# nixie_-_final1.net
KiCad netlist of a schematic drawn in EAGLE
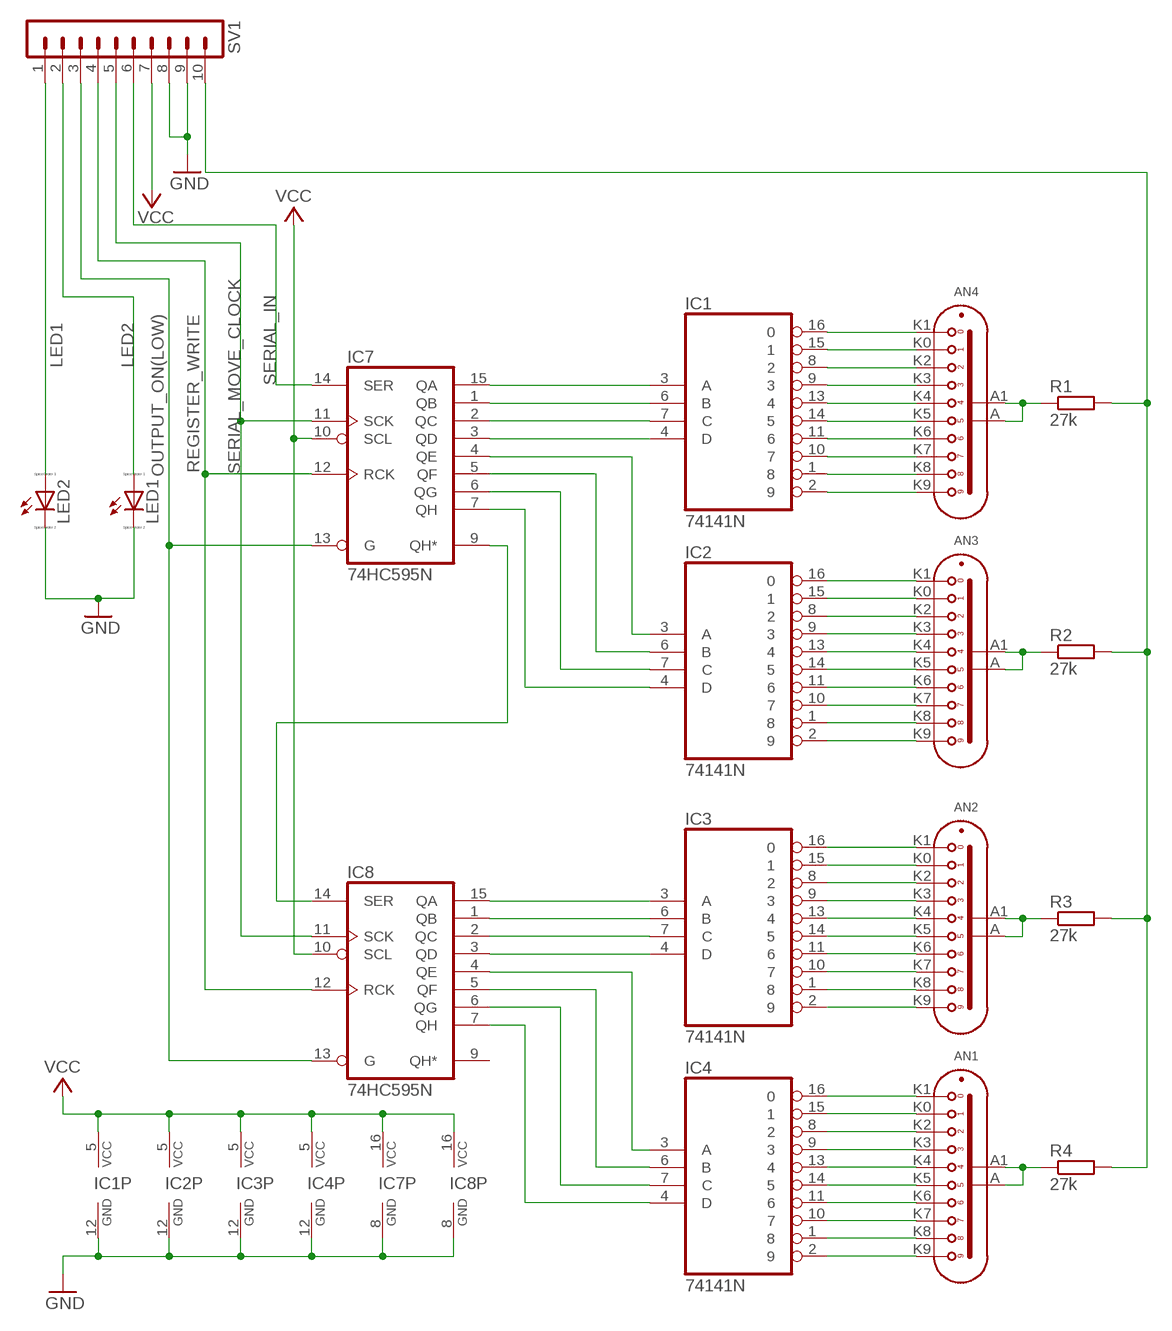
[diagram p0: schematic, sheet 1]

(export (version "E")
  (design (tool "Eeschema 10.0.6"))
  (components
    (comp (ref "AN1")
      (value "ZM1042-SOCKET_ELRADO")
      (footprint "eagle-import:ZM1040.SOCKET")
      (libsource (lib "eagle-import") (part "ZM1042-SOCKET_ELRADO"))
    )
    (comp (ref "AN2")
      (value "ZM1042-SOCKET_ELRADO")
      (footprint "eagle-import:ZM1040.SOCKET")
      (libsource (lib "eagle-import") (part "ZM1042-SOCKET_ELRADO"))
    )
    (comp (ref "AN3")
      (value "ZM1042-SOCKET_ELRADO")
      (footprint "eagle-import:ZM1040.SOCKET")
      (libsource (lib "eagle-import") (part "ZM1042-SOCKET_ELRADO"))
    )
    (comp (ref "AN4")
      (value "ZM1042-SOCKET_ELRADO")
      (footprint "eagle-import:ZM1040.SOCKET")
      (libsource (lib "eagle-import") (part "ZM1042-SOCKET_ELRADO"))
    )
    (comp (ref "IC1")
      (value "74141N")
      (footprint "eagle-import:DIL16")
      (libsource (lib "eagle-import") (part "74141N"))
    )
    (comp (ref "IC2")
      (value "74141N")
      (footprint "eagle-import:DIL16")
      (libsource (lib "eagle-import") (part "74141N"))
    )
    (comp (ref "IC3")
      (value "74141N")
      (footprint "eagle-import:DIL16")
      (libsource (lib "eagle-import") (part "74141N"))
    )
    (comp (ref "IC4")
      (value "74141N")
      (footprint "eagle-import:DIL16")
      (libsource (lib "eagle-import") (part "74141N"))
    )
    (comp (ref "IC7")
      (value "74HC595N")
      (footprint "eagle-import:DIL16")
      (libsource (lib "eagle-import") (part "74595NHC"))
    )
    (comp (ref "IC8")
      (value "74HC595N")
      (footprint "eagle-import:DIL16")
      (libsource (lib "eagle-import") (part "74595NHC"))
    )
    (comp (ref "LED1")
      (value "LED_ELD260")
      (footprint "eagle-import:LED_LD260")
      (libsource (lib "eagle-import") (part "LED_ELD260"))
    )
    (comp (ref "LED2")
      (value "LED_ELD260")
      (footprint "eagle-import:LED_LD260")
      (libsource (lib "eagle-import") (part "LED_ELD260"))
    )
    (comp (ref "R1")
      (value "27k")
      (footprint "eagle-import:0309_12")
      (libsource (lib "eagle-import") (part "R-EU_0309/12"))
    )
    (comp (ref "R2")
      (value "27k")
      (footprint "eagle-import:0309_12")
      (libsource (lib "eagle-import") (part "R-EU_0309/12"))
    )
    (comp (ref "R3")
      (value "27k")
      (footprint "eagle-import:0309_12")
      (libsource (lib "eagle-import") (part "R-EU_0309/12"))
    )
    (comp (ref "R4")
      (value "27k")
      (footprint "eagle-import:0309_12")
      (libsource (lib "eagle-import") (part "R-EU_0309/12"))
    )
    (comp (ref "SV1")
      (value "MA10-1")
      (footprint "eagle-import:MA10-1")
      (libsource (lib "eagle-import") (part "MA10-1"))
    )
  )
  (nets
    (net (code "1") (name "/LED1") (class "Default")
      (node (ref "LED2") (pin "A") (pinfunction "A_A") (pintype "passive"))
      (node (ref "SV1") (pin "1") (pinfunction "1_1") (pintype "passive"))
    )
    (net (code "2") (name "/LED2") (class "Default")
      (node (ref "LED1") (pin "A") (pinfunction "A_A") (pintype "passive"))
      (node (ref "SV1") (pin "2") (pinfunction "2_2") (pintype "passive"))
    )
    (net (code "3") (name "/OUTPUT_ON(LOW)") (class "Default")
      (node (ref "IC7") (pin "13") (pinfunction "G_13") (pintype "input"))
      (node (ref "IC8") (pin "13") (pinfunction "G_13") (pintype "input"))
      (node (ref "SV1") (pin "3") (pinfunction "3_3") (pintype "passive"))
    )
    (net (code "4") (name "/REGISTER_WRITE") (class "Default")
      (node (ref "IC7") (pin "12") (pinfunction "RCK_12") (pintype "input"))
      (node (ref "IC8") (pin "12") (pinfunction "RCK_12") (pintype "input"))
      (node (ref "SV1") (pin "4") (pinfunction "4_4") (pintype "passive"))
    )
    (net (code "5") (name "/SERIAL_IN") (class "Default")
      (node (ref "IC7") (pin "14") (pinfunction "SER_14") (pintype "input"))
      (node (ref "SV1") (pin "6") (pinfunction "6_6") (pintype "passive"))
    )
    (net (code "6") (name "/SERIAL_MOVE_CLOCK") (class "Default")
      (node (ref "IC7") (pin "11") (pinfunction "SCK_11") (pintype "input"))
      (node (ref "IC8") (pin "11") (pinfunction "SCK_11") (pintype "input"))
      (node (ref "SV1") (pin "5") (pinfunction "5_5") (pintype "passive"))
    )
    (net (code "7") (name "GND") (class "Default")
      (node (ref "IC1") (pin "12") (pinfunction "GND_12") (pintype "power_in"))
      (node (ref "IC2") (pin "12") (pinfunction "GND_12") (pintype "power_in"))
      (node (ref "IC3") (pin "12") (pinfunction "GND_12") (pintype "power_in"))
      (node (ref "IC4") (pin "12") (pinfunction "GND_12") (pintype "power_in"))
      (node (ref "IC7") (pin "8") (pinfunction "GND_8") (pintype "power_in"))
      (node (ref "IC8") (pin "8") (pinfunction "GND_8") (pintype "power_in"))
      (node (ref "LED1") (pin "K") (pinfunction "C_K") (pintype "passive"))
      (node (ref "LED2") (pin "K") (pinfunction "C_K") (pintype "passive"))
      (node (ref "SV1") (pin "8") (pinfunction "8_8") (pintype "passive"))
      (node (ref "SV1") (pin "9") (pinfunction "9_9") (pintype "passive"))
    )
    (net (code "8") (name "Net-(AN1-0)") (class "Default")
      (node (ref "AN1") (pin "K1") (pinfunction "0_K1") (pintype "passive"))
      (node (ref "IC4") (pin "16") (pinfunction "0_16") (pintype "open_collector"))
    )
    (net (code "9") (name "Net-(AN1-1)") (class "Default")
      (node (ref "AN1") (pin "K0") (pinfunction "1_K0") (pintype "passive"))
      (node (ref "IC4") (pin "15") (pinfunction "1_15") (pintype "open_collector"))
    )
    (net (code "10") (name "Net-(AN1-2)") (class "Default")
      (node (ref "AN1") (pin "K2") (pinfunction "2_K2") (pintype "passive"))
      (node (ref "IC4") (pin "8") (pinfunction "2_8") (pintype "open_collector"))
    )
    (net (code "11") (name "Net-(AN1-3)") (class "Default")
      (node (ref "AN1") (pin "K3") (pinfunction "3_K3") (pintype "passive"))
      (node (ref "IC4") (pin "9") (pinfunction "3_9") (pintype "open_collector"))
    )
    (net (code "12") (name "Net-(AN1-4)") (class "Default")
      (node (ref "AN1") (pin "K4") (pinfunction "4_K4") (pintype "passive"))
      (node (ref "IC4") (pin "13") (pinfunction "4_13") (pintype "open_collector"))
    )
    (net (code "13") (name "Net-(AN1-5)") (class "Default")
      (node (ref "AN1") (pin "K5") (pinfunction "5_K5") (pintype "passive"))
      (node (ref "IC4") (pin "14") (pinfunction "5_14") (pintype "open_collector"))
    )
    (net (code "14") (name "Net-(AN1-6)") (class "Default")
      (node (ref "AN1") (pin "K6") (pinfunction "6_K6") (pintype "passive"))
      (node (ref "IC4") (pin "11") (pinfunction "6_11") (pintype "open_collector"))
    )
    (net (code "15") (name "Net-(AN1-7)") (class "Default")
      (node (ref "AN1") (pin "K7") (pinfunction "7_K7") (pintype "passive"))
      (node (ref "IC4") (pin "10") (pinfunction "7_10") (pintype "open_collector"))
    )
    (net (code "16") (name "Net-(AN1-8)") (class "Default")
      (node (ref "AN1") (pin "K8") (pinfunction "8_K8") (pintype "passive"))
      (node (ref "IC4") (pin "1") (pinfunction "8_1") (pintype "open_collector"))
    )
    (net (code "17") (name "Net-(AN1-9)") (class "Default")
      (node (ref "AN1") (pin "K9") (pinfunction "9_K9") (pintype "passive"))
      (node (ref "IC4") (pin "2") (pinfunction "9_2") (pintype "open_collector"))
    )
    (net (code "18") (name "Net-(AN1-A1)") (class "Default")
      (node (ref "AN1") (pin "A") (pinfunction "A1_A") (pintype "passive"))
      (node (ref "AN1") (pin "A1") (pinfunction "A2_A1") (pintype "passive"))
      (node (ref "R4") (pin "1") (pinfunction "1_1") (pintype "passive"))
    )
    (net (code "19") (name "Net-(AN2-0)") (class "Default")
      (node (ref "AN2") (pin "K1") (pinfunction "0_K1") (pintype "passive"))
      (node (ref "IC3") (pin "16") (pinfunction "0_16") (pintype "open_collector"))
    )
    (net (code "20") (name "Net-(AN2-1)") (class "Default")
      (node (ref "AN2") (pin "K0") (pinfunction "1_K0") (pintype "passive"))
      (node (ref "IC3") (pin "15") (pinfunction "1_15") (pintype "open_collector"))
    )
    (net (code "21") (name "Net-(AN2-2)") (class "Default")
      (node (ref "AN2") (pin "K2") (pinfunction "2_K2") (pintype "passive"))
      (node (ref "IC3") (pin "8") (pinfunction "2_8") (pintype "open_collector"))
    )
    (net (code "22") (name "Net-(AN2-3)") (class "Default")
      (node (ref "AN2") (pin "K3") (pinfunction "3_K3") (pintype "passive"))
      (node (ref "IC3") (pin "9") (pinfunction "3_9") (pintype "open_collector"))
    )
    (net (code "23") (name "Net-(AN2-4)") (class "Default")
      (node (ref "AN2") (pin "K4") (pinfunction "4_K4") (pintype "passive"))
      (node (ref "IC3") (pin "13") (pinfunction "4_13") (pintype "open_collector"))
    )
    (net (code "24") (name "Net-(AN2-5)") (class "Default")
      (node (ref "AN2") (pin "K5") (pinfunction "5_K5") (pintype "passive"))
      (node (ref "IC3") (pin "14") (pinfunction "5_14") (pintype "open_collector"))
    )
    (net (code "25") (name "Net-(AN2-6)") (class "Default")
      (node (ref "AN2") (pin "K6") (pinfunction "6_K6") (pintype "passive"))
      (node (ref "IC3") (pin "11") (pinfunction "6_11") (pintype "open_collector"))
    )
    (net (code "26") (name "Net-(AN2-7)") (class "Default")
      (node (ref "AN2") (pin "K7") (pinfunction "7_K7") (pintype "passive"))
      (node (ref "IC3") (pin "10") (pinfunction "7_10") (pintype "open_collector"))
    )
    (net (code "27") (name "Net-(AN2-8)") (class "Default")
      (node (ref "AN2") (pin "K8") (pinfunction "8_K8") (pintype "passive"))
      (node (ref "IC3") (pin "1") (pinfunction "8_1") (pintype "open_collector"))
    )
    (net (code "28") (name "Net-(AN2-9)") (class "Default")
      (node (ref "AN2") (pin "K9") (pinfunction "9_K9") (pintype "passive"))
      (node (ref "IC3") (pin "2") (pinfunction "9_2") (pintype "open_collector"))
    )
    (net (code "29") (name "Net-(AN2-A1)") (class "Default")
      (node (ref "AN2") (pin "A") (pinfunction "A1_A") (pintype "passive"))
      (node (ref "AN2") (pin "A1") (pinfunction "A2_A1") (pintype "passive"))
      (node (ref "R3") (pin "1") (pinfunction "1_1") (pintype "passive"))
    )
    (net (code "30") (name "Net-(AN3-0)") (class "Default")
      (node (ref "AN3") (pin "K1") (pinfunction "0_K1") (pintype "passive"))
      (node (ref "IC2") (pin "16") (pinfunction "0_16") (pintype "open_collector"))
    )
    (net (code "31") (name "Net-(AN3-1)") (class "Default")
      (node (ref "AN3") (pin "K0") (pinfunction "1_K0") (pintype "passive"))
      (node (ref "IC2") (pin "15") (pinfunction "1_15") (pintype "open_collector"))
    )
    (net (code "32") (name "Net-(AN3-2)") (class "Default")
      (node (ref "AN3") (pin "K2") (pinfunction "2_K2") (pintype "passive"))
      (node (ref "IC2") (pin "8") (pinfunction "2_8") (pintype "open_collector"))
    )
    (net (code "33") (name "Net-(AN3-3)") (class "Default")
      (node (ref "AN3") (pin "K3") (pinfunction "3_K3") (pintype "passive"))
      (node (ref "IC2") (pin "9") (pinfunction "3_9") (pintype "open_collector"))
    )
    (net (code "34") (name "Net-(AN3-4)") (class "Default")
      (node (ref "AN3") (pin "K4") (pinfunction "4_K4") (pintype "passive"))
      (node (ref "IC2") (pin "13") (pinfunction "4_13") (pintype "open_collector"))
    )
    (net (code "35") (name "Net-(AN3-5)") (class "Default")
      (node (ref "AN3") (pin "K5") (pinfunction "5_K5") (pintype "passive"))
      (node (ref "IC2") (pin "14") (pinfunction "5_14") (pintype "open_collector"))
    )
    (net (code "36") (name "Net-(AN3-6)") (class "Default")
      (node (ref "AN3") (pin "K6") (pinfunction "6_K6") (pintype "passive"))
      (node (ref "IC2") (pin "11") (pinfunction "6_11") (pintype "open_collector"))
    )
    (net (code "37") (name "Net-(AN3-7)") (class "Default")
      (node (ref "AN3") (pin "K7") (pinfunction "7_K7") (pintype "passive"))
      (node (ref "IC2") (pin "10") (pinfunction "7_10") (pintype "open_collector"))
    )
    (net (code "38") (name "Net-(AN3-8)") (class "Default")
      (node (ref "AN3") (pin "K8") (pinfunction "8_K8") (pintype "passive"))
      (node (ref "IC2") (pin "1") (pinfunction "8_1") (pintype "open_collector"))
    )
    (net (code "39") (name "Net-(AN3-9)") (class "Default")
      (node (ref "AN3") (pin "K9") (pinfunction "9_K9") (pintype "passive"))
      (node (ref "IC2") (pin "2") (pinfunction "9_2") (pintype "open_collector"))
    )
    (net (code "40") (name "Net-(AN3-A1)") (class "Default")
      (node (ref "AN3") (pin "A") (pinfunction "A1_A") (pintype "passive"))
      (node (ref "AN3") (pin "A1") (pinfunction "A2_A1") (pintype "passive"))
      (node (ref "R2") (pin "1") (pinfunction "1_1") (pintype "passive"))
    )
    (net (code "41") (name "Net-(AN4-0)") (class "Default")
      (node (ref "AN4") (pin "K1") (pinfunction "0_K1") (pintype "passive"))
      (node (ref "IC1") (pin "16") (pinfunction "0_16") (pintype "open_collector"))
    )
    (net (code "42") (name "Net-(AN4-1)") (class "Default")
      (node (ref "AN4") (pin "K0") (pinfunction "1_K0") (pintype "passive"))
      (node (ref "IC1") (pin "15") (pinfunction "1_15") (pintype "open_collector"))
    )
    (net (code "43") (name "Net-(AN4-2)") (class "Default")
      (node (ref "AN4") (pin "K2") (pinfunction "2_K2") (pintype "passive"))
      (node (ref "IC1") (pin "8") (pinfunction "2_8") (pintype "open_collector"))
    )
    (net (code "44") (name "Net-(AN4-3)") (class "Default")
      (node (ref "AN4") (pin "K3") (pinfunction "3_K3") (pintype "passive"))
      (node (ref "IC1") (pin "9") (pinfunction "3_9") (pintype "open_collector"))
    )
    (net (code "45") (name "Net-(AN4-4)") (class "Default")
      (node (ref "AN4") (pin "K4") (pinfunction "4_K4") (pintype "passive"))
      (node (ref "IC1") (pin "13") (pinfunction "4_13") (pintype "open_collector"))
    )
    (net (code "46") (name "Net-(AN4-5)") (class "Default")
      (node (ref "AN4") (pin "K5") (pinfunction "5_K5") (pintype "passive"))
      (node (ref "IC1") (pin "14") (pinfunction "5_14") (pintype "open_collector"))
    )
    (net (code "47") (name "Net-(AN4-6)") (class "Default")
      (node (ref "AN4") (pin "K6") (pinfunction "6_K6") (pintype "passive"))
      (node (ref "IC1") (pin "11") (pinfunction "6_11") (pintype "open_collector"))
    )
    (net (code "48") (name "Net-(AN4-7)") (class "Default")
      (node (ref "AN4") (pin "K7") (pinfunction "7_K7") (pintype "passive"))
      (node (ref "IC1") (pin "10") (pinfunction "7_10") (pintype "open_collector"))
    )
    (net (code "49") (name "Net-(AN4-8)") (class "Default")
      (node (ref "AN4") (pin "K8") (pinfunction "8_K8") (pintype "passive"))
      (node (ref "IC1") (pin "1") (pinfunction "8_1") (pintype "open_collector"))
    )
    (net (code "50") (name "Net-(AN4-9)") (class "Default")
      (node (ref "AN4") (pin "K9") (pinfunction "9_K9") (pintype "passive"))
      (node (ref "IC1") (pin "2") (pinfunction "9_2") (pintype "open_collector"))
    )
    (net (code "51") (name "Net-(AN4-A1)") (class "Default")
      (node (ref "AN4") (pin "A") (pinfunction "A1_A") (pintype "passive"))
      (node (ref "AN4") (pin "A1") (pinfunction "A2_A1") (pintype "passive"))
      (node (ref "R1") (pin "1") (pinfunction "1_1") (pintype "passive"))
    )
    (net (code "52") (name "Net-(IC1A-A)") (class "Default")
      (node (ref "IC1") (pin "3") (pinfunction "A_3") (pintype "input"))
      (node (ref "IC7") (pin "15") (pinfunction "QA_15") (pintype "tri_state"))
    )
    (net (code "53") (name "Net-(IC1A-B)") (class "Default")
      (node (ref "IC1") (pin "6") (pinfunction "B_6") (pintype "input"))
      (node (ref "IC7") (pin "1") (pinfunction "QB_1") (pintype "tri_state"))
    )
    (net (code "54") (name "Net-(IC1A-C)") (class "Default")
      (node (ref "IC1") (pin "7") (pinfunction "C_7") (pintype "input"))
      (node (ref "IC7") (pin "2") (pinfunction "QC_2") (pintype "tri_state"))
    )
    (net (code "55") (name "Net-(IC1A-D)") (class "Default")
      (node (ref "IC1") (pin "4") (pinfunction "D_4") (pintype "input"))
      (node (ref "IC7") (pin "3") (pinfunction "QD_3") (pintype "tri_state"))
    )
    (net (code "56") (name "Net-(IC2A-A)") (class "Default")
      (node (ref "IC2") (pin "3") (pinfunction "A_3") (pintype "input"))
      (node (ref "IC7") (pin "4") (pinfunction "QE_4") (pintype "tri_state"))
    )
    (net (code "57") (name "Net-(IC2A-B)") (class "Default")
      (node (ref "IC2") (pin "6") (pinfunction "B_6") (pintype "input"))
      (node (ref "IC7") (pin "5") (pinfunction "QF_5") (pintype "tri_state"))
    )
    (net (code "58") (name "Net-(IC2A-C)") (class "Default")
      (node (ref "IC2") (pin "7") (pinfunction "C_7") (pintype "input"))
      (node (ref "IC7") (pin "6") (pinfunction "QG_6") (pintype "tri_state"))
    )
    (net (code "59") (name "Net-(IC2A-D)") (class "Default")
      (node (ref "IC2") (pin "4") (pinfunction "D_4") (pintype "input"))
      (node (ref "IC7") (pin "7") (pinfunction "QH_7") (pintype "tri_state"))
    )
    (net (code "60") (name "Net-(IC3A-A)") (class "Default")
      (node (ref "IC3") (pin "3") (pinfunction "A_3") (pintype "input"))
      (node (ref "IC8") (pin "15") (pinfunction "QA_15") (pintype "tri_state"))
    )
    (net (code "61") (name "Net-(IC3A-B)") (class "Default")
      (node (ref "IC3") (pin "6") (pinfunction "B_6") (pintype "input"))
      (node (ref "IC8") (pin "1") (pinfunction "QB_1") (pintype "tri_state"))
    )
    (net (code "62") (name "Net-(IC3A-C)") (class "Default")
      (node (ref "IC3") (pin "7") (pinfunction "C_7") (pintype "input"))
      (node (ref "IC8") (pin "2") (pinfunction "QC_2") (pintype "tri_state"))
    )
    (net (code "63") (name "Net-(IC3A-D)") (class "Default")
      (node (ref "IC3") (pin "4") (pinfunction "D_4") (pintype "input"))
      (node (ref "IC8") (pin "3") (pinfunction "QD_3") (pintype "tri_state"))
    )
    (net (code "64") (name "Net-(IC4A-A)") (class "Default")
      (node (ref "IC4") (pin "3") (pinfunction "A_3") (pintype "input"))
      (node (ref "IC8") (pin "4") (pinfunction "QE_4") (pintype "tri_state"))
    )
    (net (code "65") (name "Net-(IC4A-B)") (class "Default")
      (node (ref "IC4") (pin "6") (pinfunction "B_6") (pintype "input"))
      (node (ref "IC8") (pin "5") (pinfunction "QF_5") (pintype "tri_state"))
    )
    (net (code "66") (name "Net-(IC4A-C)") (class "Default")
      (node (ref "IC4") (pin "7") (pinfunction "C_7") (pintype "input"))
      (node (ref "IC8") (pin "6") (pinfunction "QG_6") (pintype "tri_state"))
    )
    (net (code "67") (name "Net-(IC4A-D)") (class "Default")
      (node (ref "IC4") (pin "4") (pinfunction "D_4") (pintype "input"))
      (node (ref "IC8") (pin "7") (pinfunction "QH_7") (pintype "tri_state"))
    )
    (net (code "68") (name "Net-(IC7A-QH*)") (class "Default")
      (node (ref "IC7") (pin "9") (pinfunction "QH*_9") (pintype "tri_state"))
      (node (ref "IC8") (pin "14") (pinfunction "SER_14") (pintype "input"))
    )
    (net (code "69") (name "Net-(R1-Pad2)") (class "Default")
      (node (ref "R1") (pin "2") (pinfunction "2_2") (pintype "passive"))
      (node (ref "R2") (pin "2") (pinfunction "2_2") (pintype "passive"))
      (node (ref "R3") (pin "2") (pinfunction "2_2") (pintype "passive"))
      (node (ref "R4") (pin "2") (pinfunction "2_2") (pintype "passive"))
      (node (ref "SV1") (pin "10") (pinfunction "10_10") (pintype "passive"))
    )
    (net (code "70") (name "VCC") (class "Default")
      (node (ref "IC1") (pin "5") (pinfunction "VCC_5") (pintype "power_in"))
      (node (ref "IC2") (pin "5") (pinfunction "VCC_5") (pintype "power_in"))
      (node (ref "IC3") (pin "5") (pinfunction "VCC_5") (pintype "power_in"))
      (node (ref "IC4") (pin "5") (pinfunction "VCC_5") (pintype "power_in"))
      (node (ref "IC7") (pin "10") (pinfunction "SCL_10") (pintype "input"))
      (node (ref "IC7") (pin "16") (pinfunction "VCC_16") (pintype "power_in"))
      (node (ref "IC8") (pin "10") (pinfunction "SCL_10") (pintype "input"))
      (node (ref "IC8") (pin "16") (pinfunction "VCC_16") (pintype "power_in"))
      (node (ref "SV1") (pin "7") (pinfunction "7_7") (pintype "passive"))
    )
    (net (code "71") (name "unconnected-(IC8A-QH*-Pad9)") (class "Default")
      (node (ref "IC8") (pin "9") (pinfunction "QH*_9") (pintype "tri_state"))
    )
  )
)
